# VlakecDuplo.net
KiCad netlist of a schematic drawn in Altium Designer
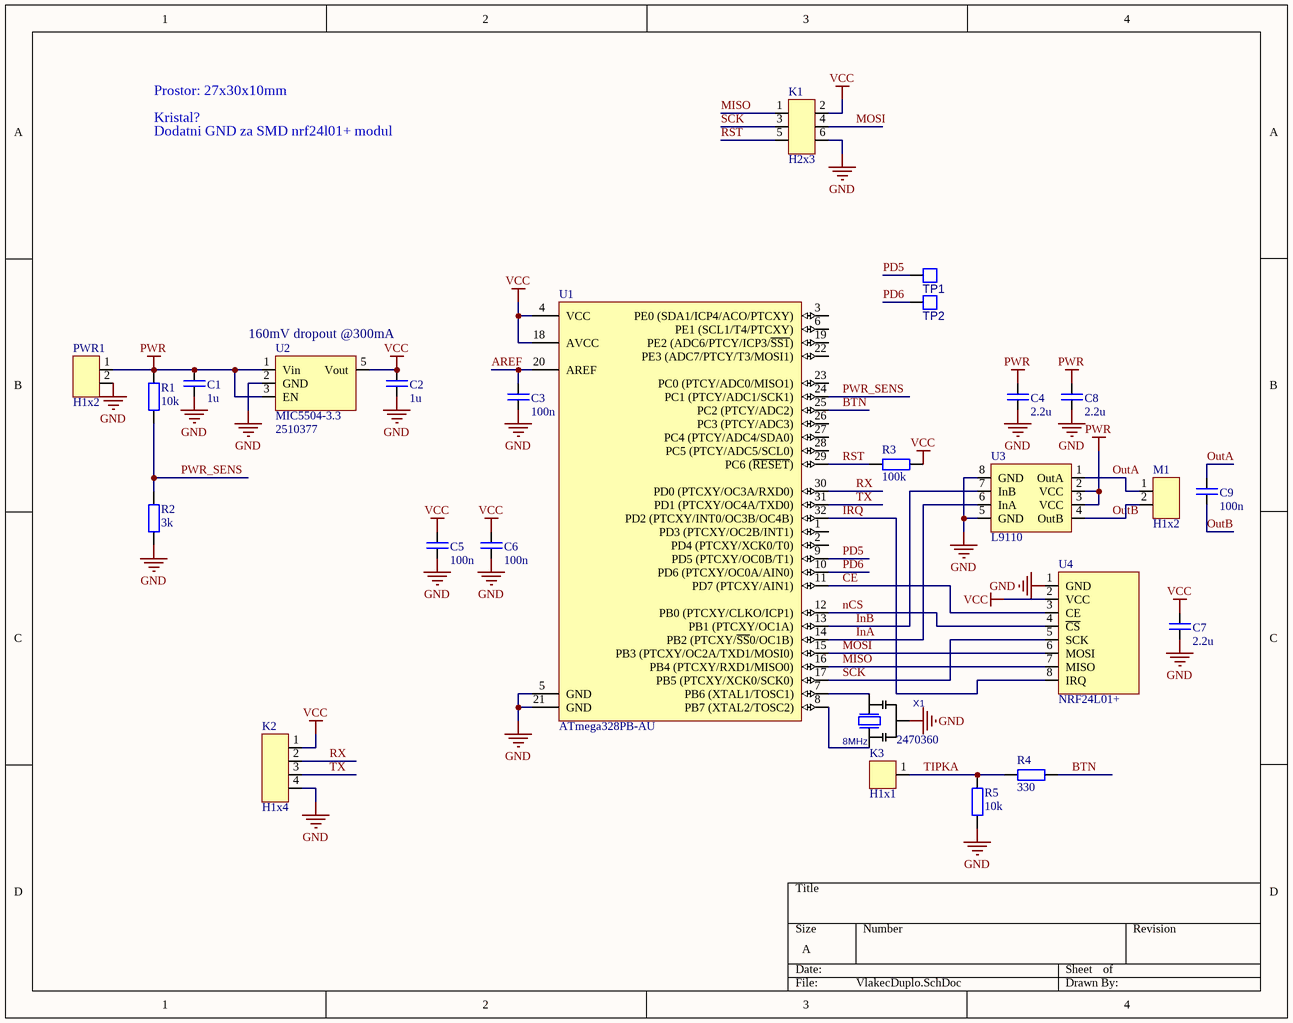
[diagram p0: VlakecDuplo.SchDoc]

(export (version "E")
  (design (tool "Eeschema 10.0.6"))
  (components
    (comp (ref "C1")
      (value "1u")
      (footprint "C0805(2012)_N")
      (description "Capacitor")
      (libsource (lib "General") (part "C"))
    )
    (comp (ref "C2")
      (value "1u")
      (footprint "C0805(2012)_N")
      (description "Capacitor")
      (libsource (lib "General") (part "C"))
    )
    (comp (ref "C3")
      (value "100n")
      (footprint "C0805(2012)_N")
      (description "Capacitor")
      (libsource (lib "General") (part "C"))
    )
    (comp (ref "C4")
      (value "2.2u")
      (footprint "C0805(2012)_N")
      (description "Capacitor")
      (libsource (lib "General") (part "C"))
    )
    (comp (ref "C5")
      (value "100n")
      (footprint "C0805(2012)_N")
      (description "Capacitor")
      (libsource (lib "General") (part "C"))
    )
    (comp (ref "C6")
      (value "100n")
      (footprint "C0805(2012)_N")
      (description "Capacitor")
      (libsource (lib "General") (part "C"))
    )
    (comp (ref "C7")
      (value "2.2u")
      (footprint "C0805(2012)_N")
      (description "Capacitor")
      (libsource (lib "General") (part "C"))
    )
    (comp (ref "C8")
      (value "2.2u")
      (footprint "C0805(2012)_N")
      (description "Capacitor")
      (libsource (lib "General") (part "C"))
    )
    (comp (ref "C9")
      (value "100n")
      (footprint "C0805(2012)_N")
      (description "Capacitor")
      (libsource (lib "General") (part "C"))
    )
    (comp (ref "K1")
      (value "H2x3")
      (footprint "H2X3_SPEEDY")
      (description "Header 2x3 (male)")
      (libsource (lib "MISKO V2_1") (part "H2x3"))
    )
    (comp (ref "K2")
      (value "H1x4")
      (footprint "H1x4")
      (description "Header 1x4 (male)")
      (libsource (lib "Kon_Tipk") (part "H1x4"))
    )
    (comp (ref "K3")
      (value "H1x1")
      (footprint "H1x1")
      (description "Header 1x1 (male)")
      (libsource (lib "Kon_Tipk") (part "H1x1"))
    )
    (comp (ref "M1")
      (value "H1x2")
      (footprint "H1x2")
      (description "Header 1x2 (male)")
      (libsource (lib "MISKO V2_1") (part "H1x2"))
    )
    (comp (ref "PWR1")
      (value "H1x2")
      (footprint "H1x2")
      (description "Header 1x2 (male)")
      (libsource (lib "") (part "H1x2_1"))
    )
    (comp (ref "R1")
      (value "10k")
      (footprint "R0805(2012)_N")
      (description "R")
      (libsource (lib "General") (part "R"))
    )
    (comp (ref "R2")
      (value "3k")
      (footprint "R0805(2012)_N")
      (description "R")
      (libsource (lib "General") (part "R"))
    )
    (comp (ref "R3")
      (value "100k")
      (footprint "R0805(2012)_N")
      (description "R")
      (libsource (lib "General") (part "R"))
    )
    (comp (ref "R4")
      (value "330")
      (footprint "R0805(2012)_N")
      (description "R")
      (libsource (lib "General") (part "R"))
    )
    (comp (ref "R5")
      (value "10k")
      (footprint "R0805(2012)_N")
      (description "R")
      (libsource (lib "General") (part "R"))
    )
    (comp (ref "TP1")
      (value "PD5")
      (footprint "PAD_HOLE")
      (description "PAD")
      (libsource (lib "General") (part "PAD"))
    )
    (comp (ref "TP2")
      (value "PD6")
      (footprint "PAD_HOLE")
      (description "PAD")
      (libsource (lib "General") (part "PAD"))
    )
    (comp (ref "U1")
      (value "ATmega328PB-AU")
      (footprint "32A_N")
      (libsource (lib "MISKO V2_1") (part "ATmega328PB-AU"))
    )
    (comp (ref "U2")
      (value "MIC5504-3.3")
      (footprint "SOT23-5")
      (fields (field (name "SUPPLIER PART NUMBER 1") "2510377"))
      (libsource (lib "Vlakec") (part "MIC5504-3.3"))
    )
    (comp (ref "U3") (value "L9110") (footprint "SOP-8") (libsource (lib "Vlakec") (part "L9110")))
    (comp (ref "U4")
      (value "NRF24L01+")
      (footprint "NRF24L01+smd_module")
      (libsource (lib "Modules") (part "NRF24L01+"))
    )
    (comp (ref "X1")
      (value "8MHz")
      (footprint "RESONATOR_3213met_L")
      (description "Crystal")
      (fields (field (name "SUPPLIER PART NUMBER 1") "2470360"))
      (libsource (lib "General") (part "ResonatorWCaps"))
    )
  )
  (nets
    (net (code "1") (name "/AREF") (class "Default")
      (node (ref "C3") (pin "1") (pinfunction "1_1") (pintype "passive"))
      (node (ref "U1") (pin "20") (pinfunction "AREF_20") (pintype "passive"))
    )
    (net (code "2") (name "/BTN") (class "Default")
      (node (ref "R4") (pin "2") (pintype "passive"))
      (node (ref "U1") (pin "25") (pinfunction "PC2_(PTCY/ADC2)_25") (pintype "bidirectional"))
    )
    (net (code "3") (name "/CE") (class "Default")
      (node (ref "U1") (pin "11") (pinfunction "PD7_(PTCXY/AIN1)_11") (pintype "bidirectional"))
      (node (ref "U4") (pin "3") (pinfunction "CE_3") (pintype "passive"))
    )
    (net (code "4") (name "/IRQ") (class "Default")
      (node (ref "U1") (pin "32") (pinfunction "PD2_(PTCXY/INT0/OC3B/OC4B)_32") (pintype "bidirectional"))
      (node (ref "U4") (pin "8") (pinfunction "IRQ_8") (pintype "passive"))
    )
    (net (code "5") (name "/InA") (class "Default")
      (node (ref "U1") (pin "14") (pinfunction "PB2_(PTCXY/~{SS}0/OC1B)_14") (pintype "bidirectional"))
      (node (ref "U3") (pin "6") (pinfunction "InA_6") (pintype "passive"))
    )
    (net (code "6") (name "/InB") (class "Default")
      (node (ref "U1") (pin "13") (pinfunction "PB1_(PTCXY/OC1A)_13") (pintype "bidirectional"))
      (node (ref "U3") (pin "7") (pinfunction "InB_7") (pintype "passive"))
    )
    (net (code "7") (name "/MISO") (class "Default")
      (node (ref "K1") (pin "1") (pinfunction "1_1") (pintype "passive"))
      (node (ref "U1") (pin "16") (pinfunction "PB4_(PTCXY/RXD1/MISO0)_16") (pintype "bidirectional"))
      (node (ref "U4") (pin "7") (pinfunction "MISO_7") (pintype "passive"))
    )
    (net (code "8") (name "/MOSI") (class "Default")
      (node (ref "K1") (pin "4") (pinfunction "4_4") (pintype "passive"))
      (node (ref "U1") (pin "15") (pinfunction "PB3_(PTCXY/OC2A/TXD1/MOSI0)_15") (pintype "bidirectional"))
      (node (ref "U4") (pin "6") (pinfunction "MOSI_6") (pintype "passive"))
    )
    (net (code "9") (name "/OutA") (class "Default")
      (node (ref "C9") (pin "1") (pinfunction "1_1") (pintype "passive"))
      (node (ref "M1") (pin "1") (pinfunction "1_1") (pintype "passive"))
      (node (ref "U3") (pin "1") (pinfunction "OutA_1") (pintype "passive"))
    )
    (net (code "10") (name "/OutB") (class "Default")
      (node (ref "C9") (pin "2") (pinfunction "2_2") (pintype "passive"))
      (node (ref "M1") (pin "2") (pinfunction "2_2") (pintype "passive"))
      (node (ref "U3") (pin "4") (pinfunction "OutB_4") (pintype "passive"))
    )
    (net (code "11") (name "/PD5") (class "Default")
      (node (ref "TP1") (pin "1") (pinfunction "1_1") (pintype "passive"))
      (node (ref "U1") (pin "9") (pinfunction "PD5_(PTCXY/OC0B/T1)_9") (pintype "bidirectional"))
    )
    (net (code "12") (name "/PD6") (class "Default")
      (node (ref "TP2") (pin "1") (pinfunction "1_1") (pintype "passive"))
      (node (ref "U1") (pin "10") (pinfunction "PD6_(PTCXY/OC0A/AIN0)_10") (pintype "bidirectional"))
    )
    (net (code "13") (name "/PWR_SENS") (class "Default")
      (node (ref "R1") (pin "2") (pintype "passive"))
      (node (ref "R2") (pin "1") (pintype "passive"))
      (node (ref "U1") (pin "24") (pinfunction "PC1_(PTCY/ADC1/SCK1)_24") (pintype "bidirectional"))
    )
    (net (code "14") (name "/RST") (class "Default")
      (node (ref "K1") (pin "5") (pinfunction "5_5") (pintype "passive"))
      (node (ref "R3") (pin "1") (pintype "passive"))
      (node (ref "U1") (pin "29") (pinfunction "PC6_(~{RESET})_29") (pintype "bidirectional"))
    )
    (net (code "15") (name "/RX") (class "Default")
      (node (ref "K2") (pin "2") (pinfunction "2_2") (pintype "passive"))
      (node (ref "U1") (pin "30") (pinfunction "PD0_(PTCXY/OC3A/RXD0)_30") (pintype "bidirectional"))
    )
    (net (code "16") (name "/SCK") (class "Default")
      (node (ref "K1") (pin "3") (pinfunction "3_3") (pintype "passive"))
      (node (ref "U1") (pin "17") (pinfunction "PB5_(PTCXY/XCK0/SCK0)_17") (pintype "bidirectional"))
      (node (ref "U4") (pin "5") (pinfunction "SCK_5") (pintype "passive"))
    )
    (net (code "17") (name "/TIPKA") (class "Default")
      (node (ref "K3") (pin "1") (pinfunction "1_1") (pintype "passive"))
      (node (ref "R4") (pin "1") (pintype "passive"))
      (node (ref "R5") (pin "1") (pintype "passive"))
    )
    (net (code "18") (name "/TX") (class "Default")
      (node (ref "K2") (pin "3") (pinfunction "3_3") (pintype "passive"))
      (node (ref "U1") (pin "31") (pinfunction "PD1_(PTCXY/OC4A/TXD0)_31") (pintype "bidirectional"))
    )
    (net (code "19") (name "/nCS") (class "Default")
      (node (ref "U1") (pin "12") (pinfunction "PB0_(PTCXY/CLKO/ICP1)_12") (pintype "bidirectional"))
      (node (ref "U4") (pin "4") (pinfunction "~{CS}_4") (pintype "passive"))
    )
    (net (code "20") (name "GND") (class "Default")
      (node (ref "C1") (pin "2") (pinfunction "2_2") (pintype "passive"))
      (node (ref "C2") (pin "2") (pinfunction "2_2") (pintype "passive"))
      (node (ref "C3") (pin "2") (pinfunction "2_2") (pintype "passive"))
      (node (ref "C4") (pin "2") (pinfunction "2_2") (pintype "passive"))
      (node (ref "C5") (pin "2") (pinfunction "2_2") (pintype "passive"))
      (node (ref "C6") (pin "2") (pinfunction "2_2") (pintype "passive"))
      (node (ref "C7") (pin "2") (pinfunction "2_2") (pintype "passive"))
      (node (ref "C8") (pin "2") (pinfunction "2_2") (pintype "passive"))
      (node (ref "K1") (pin "6") (pinfunction "6_6") (pintype "passive"))
      (node (ref "K2") (pin "4") (pinfunction "4_4") (pintype "passive"))
      (node (ref "PWR1") (pin "2") (pinfunction "2_2") (pintype "passive"))
      (node (ref "R2") (pin "2") (pintype "passive"))
      (node (ref "R5") (pin "2") (pintype "passive"))
      (node (ref "U1") (pin "21") (pinfunction "GND_21") (pintype "power_in"))
      (node (ref "U1") (pin "5") (pinfunction "GND_5") (pintype "power_in"))
      (node (ref "U2") (pin "2") (pinfunction "GND_2") (pintype "passive"))
      (node (ref "U3") (pin "5") (pinfunction "GND_5") (pintype "passive"))
      (node (ref "U3") (pin "8") (pinfunction "GND_8") (pintype "passive"))
      (node (ref "U4") (pin "1") (pinfunction "GND_1") (pintype "passive"))
      (node (ref "X1") (pin "2") (pinfunction "GND_2") (pintype "passive"))
    )
    (net (code "21") (name "Net-(U1-PB6_(XTAL1{slash}TOSC1))") (class "Default")
      (node (ref "U1") (pin "7") (pinfunction "PB6_(XTAL1/TOSC1)_7") (pintype "bidirectional"))
      (node (ref "X1") (pin "3") (pinfunction "2_3") (pintype "passive"))
    )
    (net (code "22") (name "Net-(U1-PB7_(XTAL2{slash}TOSC2))") (class "Default")
      (node (ref "U1") (pin "8") (pinfunction "PB7_(XTAL2/TOSC2)_8") (pintype "bidirectional"))
      (node (ref "X1") (pin "1") (pinfunction "1_1") (pintype "passive"))
    )
    (net (code "23") (name "PWR") (class "Default")
      (node (ref "C1") (pin "1") (pinfunction "1_1") (pintype "passive"))
      (node (ref "C4") (pin "1") (pinfunction "1_1") (pintype "passive"))
      (node (ref "C8") (pin "1") (pinfunction "1_1") (pintype "passive"))
      (node (ref "PWR1") (pin "1") (pinfunction "1_1") (pintype "passive"))
      (node (ref "R1") (pin "1") (pintype "passive"))
      (node (ref "U2") (pin "1") (pinfunction "Vin_1") (pintype "passive"))
      (node (ref "U2") (pin "3") (pinfunction "EN_3") (pintype "passive"))
      (node (ref "U3") (pin "2") (pinfunction "VCC_2") (pintype "passive"))
      (node (ref "U3") (pin "3") (pinfunction "VCC_3") (pintype "passive"))
    )
    (net (code "24") (name "VCC") (class "Default")
      (node (ref "C2") (pin "1") (pinfunction "1_1") (pintype "passive"))
      (node (ref "C5") (pin "1") (pinfunction "1_1") (pintype "passive"))
      (node (ref "C6") (pin "1") (pinfunction "1_1") (pintype "passive"))
      (node (ref "C7") (pin "1") (pinfunction "1_1") (pintype "passive"))
      (node (ref "K1") (pin "2") (pinfunction "2_2") (pintype "passive"))
      (node (ref "K2") (pin "1") (pinfunction "1_1") (pintype "passive"))
      (node (ref "R3") (pin "2") (pintype "passive"))
      (node (ref "U1") (pin "18") (pinfunction "AVCC_18") (pintype "power_in"))
      (node (ref "U1") (pin "4") (pinfunction "VCC_4") (pintype "power_in"))
      (node (ref "U2") (pin "5") (pinfunction "Vout_5") (pintype "passive"))
      (node (ref "U4") (pin "2") (pinfunction "VCC_2") (pintype "passive"))
    )
    (net (code "25") (name "unconnected-(U1-PC0_(PTCY{slash}ADC0{slash}MISO1)-Pad23)") (class "Default")
      (node (ref "U1") (pin "23") (pinfunction "PC0_(PTCY/ADC0/MISO1)_23") (pintype "bidirectional"))
    )
    (net (code "26") (name "unconnected-(U1-PC3_(PTCY{slash}ADC3)-Pad26)") (class "Default")
      (node (ref "U1") (pin "26") (pinfunction "PC3_(PTCY/ADC3)_26") (pintype "bidirectional"))
    )
    (net (code "27") (name "unconnected-(U1-PC4_(PTCY{slash}ADC4{slash}SDA0)-Pad27)") (class "Default")
      (node (ref "U1") (pin "27") (pinfunction "PC4_(PTCY/ADC4/SDA0)_27") (pintype "bidirectional"))
    )
    (net (code "28") (name "unconnected-(U1-PC5_(PTCY{slash}ADC5{slash}SCL0)-Pad28)") (class "Default")
      (node (ref "U1") (pin "28") (pinfunction "PC5_(PTCY/ADC5/SCL0)_28") (pintype "bidirectional"))
    )
    (net (code "29") (name "unconnected-(U1-PD3_(PTCXY{slash}OC2B{slash}INT1)-Pad1)") (class "Default")
      (node (ref "U1") (pin "1") (pinfunction "PD3_(PTCXY/OC2B/INT1)_1") (pintype "bidirectional"))
    )
    (net (code "30") (name "unconnected-(U1-PD4_(PTCXY{slash}XCK0{slash}T0)-Pad2)") (class "Default")
      (node (ref "U1") (pin "2") (pinfunction "PD4_(PTCXY/XCK0/T0)_2") (pintype "bidirectional"))
    )
    (net (code "31") (name "unconnected-(U1-PE0_(SDA1{slash}ICP4{slash}ACO{slash}PTCXY)-Pad3)") (class "Default")
      (node (ref "U1") (pin "3") (pinfunction "PE0_(SDA1/ICP4/ACO/PTCXY)_3") (pintype "bidirectional"))
    )
    (net (code "32") (name "unconnected-(U1-PE1_(SCL1{slash}T4{slash}PTCXY)-Pad6)") (class "Default")
      (node (ref "U1") (pin "6") (pinfunction "PE1_(SCL1/T4/PTCXY)_6") (pintype "bidirectional"))
    )
    (net (code "33") (name "unconnected-(U1-PE2_(ADC6{slash}PTCY{slash}ICP3{slash}~{SS1})-Pad19)") (class "Default")
      (node (ref "U1") (pin "19") (pinfunction "PE2_(ADC6/PTCY/ICP3/~{SS1})_19") (pintype "bidirectional"))
    )
    (net (code "34") (name "unconnected-(U1-PE3_(ADC7{slash}PTCY{slash}T3{slash}MOSI1)-Pad22)") (class "Default")
      (node (ref "U1") (pin "22") (pinfunction "PE3_(ADC7/PTCY/T3/MOSI1)_22") (pintype "bidirectional"))
    )
  )
)
